# Laser_Shield_Eth.net
KiCad netlist of a schematic drawn in EAGLE
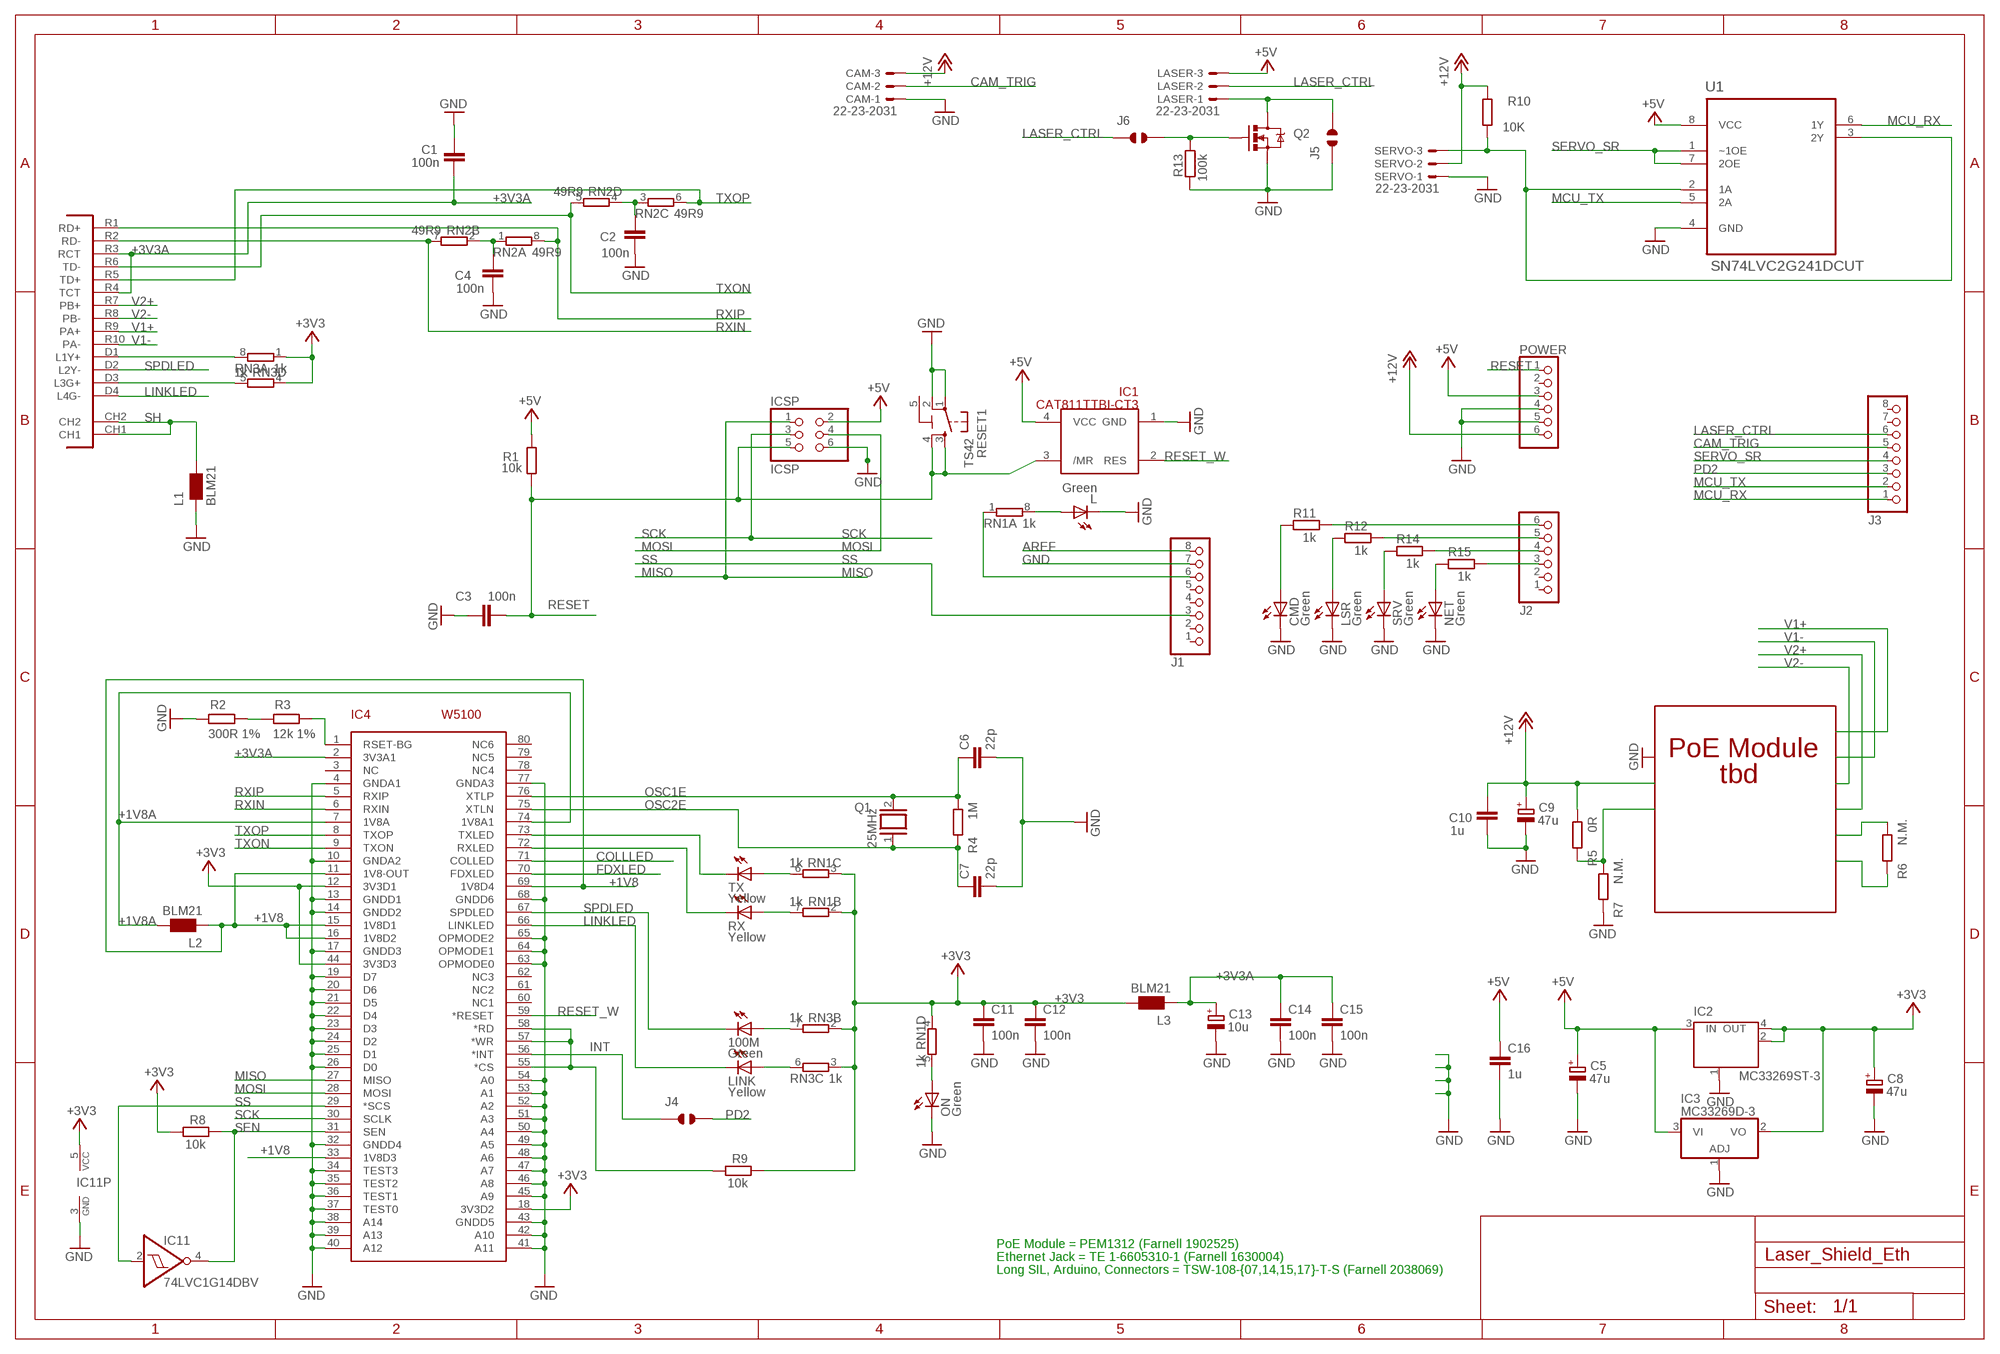
[diagram p0: schematic, sheet 1]

(export (version "E")
  (design (tool "Eeschema 10.0.6"))
  (components
    (comp (ref "100M")
      (value "Green")
      (footprint "eagle-import:CHIPLED_0805")
      (libsource (lib "eagle-import") (part "LEDCHIPLED_0805"))
    )
    (comp (ref "C1")
      (value "100n")
      (footprint "eagle-import:C0603-ROUND")
      (libsource (lib "eagle-import") (part "C-EUC0603"))
    )
    (comp (ref "C2")
      (value "100n")
      (footprint "eagle-import:C0603-ROUND")
      (libsource (lib "eagle-import") (part "C-EUC0603"))
    )
    (comp (ref "C3")
      (value "100n")
      (footprint "eagle-import:C0603-ROUND")
      (libsource (lib "eagle-import") (part "C-EUC0603"))
    )
    (comp (ref "C4")
      (value "100n")
      (footprint "eagle-import:C0603-ROUND")
      (libsource (lib "eagle-import") (part "C-EUC0603"))
    )
    (comp (ref "C5")
      (value "47u")
      (footprint "eagle-import:PANASONIC_D")
      (libsource (lib "eagle-import") (part "CPOL-EUD"))
    )
    (comp (ref "C6")
      (value "22p")
      (footprint "eagle-import:C0603-ROUND")
      (libsource (lib "eagle-import") (part "C-EUC0603"))
    )
    (comp (ref "C7")
      (value "22p")
      (footprint "eagle-import:C0603-ROUND")
      (libsource (lib "eagle-import") (part "C-EUC0603"))
    )
    (comp (ref "C8")
      (value "47u")
      (footprint "eagle-import:PANASONIC_D")
      (libsource (lib "eagle-import") (part "CPOL-EUD"))
    )
    (comp (ref "C9")
      (value "47u")
      (footprint "eagle-import:PANASONIC_D")
      (libsource (lib "eagle-import") (part "CPOL-EUD"))
    )
    (comp (ref "C10")
      (value "1u")
      (footprint "eagle-import:C0603-ROUND")
      (libsource (lib "eagle-import") (part "C-EUC0603"))
    )
    (comp (ref "C11")
      (value "100n")
      (footprint "eagle-import:C0603-ROUND")
      (libsource (lib "eagle-import") (part "C-EUC0603"))
    )
    (comp (ref "C12")
      (value "100n")
      (footprint "eagle-import:C0603-ROUND")
      (libsource (lib "eagle-import") (part "C-EUC0603"))
    )
    (comp (ref "C13")
      (value "10u")
      (footprint "eagle-import:SMC_B")
      (libsource (lib "eagle-import") (part "CPOL-EUSMCB"))
    )
    (comp (ref "C14")
      (value "100n")
      (footprint "eagle-import:C0603-ROUND")
      (libsource (lib "eagle-import") (part "C-EUC0603"))
    )
    (comp (ref "C15")
      (value "100n")
      (footprint "eagle-import:C0603-ROUND")
      (libsource (lib "eagle-import") (part "C-EUC0603"))
    )
    (comp (ref "C16")
      (value "1u")
      (footprint "eagle-import:C0603-ROUND")
      (libsource (lib "eagle-import") (part "C-EUC0603"))
    )
    (comp (ref "CAM")
      (value "22-23-2031")
      (footprint "eagle-import:22-23-2031")
      (fields (field (name "MF") "MOLEX"))
      (libsource (lib "eagle-import") (part "22-23-2031"))
    )
    (comp (ref "CMD")
      (value "Green")
      (footprint "eagle-import:CHIPLED_0805")
      (libsource (lib "eagle-import") (part "LEDCHIPLED_0805"))
    )
    (comp (ref "IC1")
      (value "CAT811TTBI-CT3")
      (footprint "eagle-import:SOT143")
      (fields (field (name "MPN") "STM812LW16F"))
      (libsource (lib "eagle-import") (part "STM812"))
    )
    (comp (ref "IC2")
      (value "MC33269ST-3")
      (footprint "eagle-import:SOT223")
      (libsource (lib "eagle-import") (part "MC33269ST-3.3T3"))
    )
    (comp (ref "IC3")
      (value "MC33269D-3")
      (footprint "eagle-import:DPACK")
      (libsource (lib "eagle-import") (part "MC33269?D-3.3"))
    )
    (comp (ref "IC4")
      (value "W5100")
      (footprint "eagle-import:SQFP-S-10X10-80")
      (libsource (lib "eagle-import") (part "W5100"))
    )
    (comp (ref "IC11")
      (value "74LVC1G14DBV")
      (footprint "eagle-import:SOT23-5")
      (fields (field (name "MPN") "SN74LVC1G14DBVT") (field (name "OC_FARNELL") "1236328"))
      (libsource (lib "eagle-import") (part "741G14DBVLVC"))
    )
    (comp (ref "ICSP")
      (value "ICSP")
      (footprint "eagle-import:2X03")
      (libsource (lib "eagle-import") (part "PINHD-2X3"))
    )
    (comp (ref "J1")
      (value "PINHD-1X8")
      (footprint "eagle-import:1X08")
      (libsource (lib "eagle-import") (part "PINHD-1X8"))
    )
    (comp (ref "J2")
      (value "PINHD-1X6")
      (footprint "eagle-import:1X06")
      (libsource (lib "eagle-import") (part "PINHD-1X6"))
    )
    (comp (ref "J3")
      (value "PINHD-1X8")
      (footprint "eagle-import:1X08")
      (libsource (lib "eagle-import") (part "PINHD-1X8"))
    )
    (comp (ref "J4")
      (value "JUMPER_SOLDER_1X2")
      (footprint "eagle-import:JUMPER_SOLDER_1X2")
      (libsource (lib "eagle-import") (part "JUMPER_SOLDER_1X2"))
    )
    (comp (ref "J5")
      (value "JUMPER_SOLDER_1X2")
      (footprint "eagle-import:JUMPER_SOLDER_1X2")
      (libsource (lib "eagle-import") (part "JUMPER_SOLDER_1X2"))
    )
    (comp (ref "J6")
      (value "JUMPER_SOLDER_1X2")
      (footprint "eagle-import:JUMPER_SOLDER_1X2")
      (libsource (lib "eagle-import") (part "JUMPER_SOLDER_1X2"))
    )
    (comp (ref "L")
      (value "Green")
      (footprint "eagle-import:CHIPLED_0805")
      (libsource (lib "eagle-import") (part "LEDCHIPLED_0805"))
    )
    (comp (ref "L1")
      (value "BLM21")
      (footprint "eagle-import:0805")
      (libsource (lib "eagle-import") (part "WE-CBF_0805"))
    )
    (comp (ref "L2")
      (value "BLM21")
      (footprint "eagle-import:0805")
      (libsource (lib "eagle-import") (part "WE-CBF_0805"))
    )
    (comp (ref "L3")
      (value "BLM21")
      (footprint "eagle-import:0805")
      (libsource (lib "eagle-import") (part "WE-CBF_0805"))
    )
    (comp (ref "LASER")
      (value "22-23-2031")
      (footprint "eagle-import:22-23-2031")
      (fields (field (name "MF") "MOLEX"))
      (libsource (lib "eagle-import") (part "22-23-2031"))
    )
    (comp (ref "LINK")
      (value "Yellow")
      (footprint "eagle-import:CHIPLED_0805")
      (libsource (lib "eagle-import") (part "LEDCHIPLED_0805"))
    )
    (comp (ref "LSR")
      (value "Green")
      (footprint "eagle-import:CHIPLED_0805")
      (libsource (lib "eagle-import") (part "LEDCHIPLED_0805"))
    )
    (comp (ref "NET")
      (value "Green")
      (footprint "eagle-import:CHIPLED_0805")
      (libsource (lib "eagle-import") (part "LEDCHIPLED_0805"))
    )
    (comp (ref "ON")
      (value "Green")
      (footprint "eagle-import:CHIPLED_0805")
      (libsource (lib "eagle-import") (part "LEDCHIPLED_0805"))
    )
    (comp (ref "POWER")
      (value "PINHD-1X6")
      (footprint "eagle-import:1X06")
      (libsource (lib "eagle-import") (part "PINHD-1X6"))
    )
    (comp (ref "Q1")
      (value "25MHz")
      (footprint "eagle-import:QS")
      (libsource (lib "eagle-import") (part "XTAL/S"))
    )
    (comp (ref "Q2")
      (value "MOSFET-NCHANNELSMD")
      (footprint "eagle-import:SOT23-3")
      (libsource (lib "eagle-import") (part "MOSFET-NCHANNELSMD"))
    )
    (comp (ref "R1")
      (value "10k")
      (footprint "eagle-import:R0603-ROUND")
      (libsource (lib "eagle-import") (part "R-EU_0603-RND"))
    )
    (comp (ref "R2")
      (value "300R 1%")
      (footprint "eagle-import:R0603-ROUND")
      (libsource (lib "eagle-import") (part "R-EU_0603-RND"))
    )
    (comp (ref "R3")
      (value "12k 1%")
      (footprint "eagle-import:R0603-ROUND")
      (libsource (lib "eagle-import") (part "R-EU_0603-RND"))
    )
    (comp (ref "R4")
      (value "1M")
      (footprint "eagle-import:R0603-ROUND")
      (libsource (lib "eagle-import") (part "R-EU_0603-RND"))
    )
    (comp (ref "R5")
      (value "0R")
      (footprint "eagle-import:R0603-ROUND")
      (libsource (lib "eagle-import") (part "R-EU_0603-RND"))
    )
    (comp (ref "R6")
      (value "N.M.")
      (footprint "eagle-import:R0603-ROUND")
      (libsource (lib "eagle-import") (part "R-EU_0603-RND"))
    )
    (comp (ref "R7")
      (value "N.M.")
      (footprint "eagle-import:R0603-ROUND")
      (libsource (lib "eagle-import") (part "R-EU_0603-RND"))
    )
    (comp (ref "R8")
      (value "10k")
      (footprint "eagle-import:R0603-ROUND")
      (libsource (lib "eagle-import") (part "R-EU_0603-RND"))
    )
    (comp (ref "R9")
      (value "10k")
      (footprint "eagle-import:R0603-ROUND")
      (libsource (lib "eagle-import") (part "R-EU_R0603"))
    )
    (comp (ref "R10")
      (value "10K")
      (footprint "eagle-import:R0603-ROUND")
      (libsource (lib "eagle-import") (part "R-EU_0603-RND"))
    )
    (comp (ref "R11")
      (value "1k")
      (footprint "eagle-import:R0603-ROUND")
      (libsource (lib "eagle-import") (part "R-EU_R0603"))
    )
    (comp (ref "R12")
      (value "1k")
      (footprint "eagle-import:R0603-ROUND")
      (libsource (lib "eagle-import") (part "R-EU_R0603"))
    )
    (comp (ref "R13")
      (value "100k")
      (footprint "eagle-import:R0603-ROUND")
      (libsource (lib "eagle-import") (part "R-EU_R0603"))
    )
    (comp (ref "R14")
      (value "1k")
      (footprint "eagle-import:R0603-ROUND")
      (libsource (lib "eagle-import") (part "R-EU_R0603"))
    )
    (comp (ref "R15")
      (value "1k")
      (footprint "eagle-import:R0603-ROUND")
      (libsource (lib "eagle-import") (part "R-EU_R0603"))
    )
    (comp (ref "RESET1")
      (value "TS42")
      (footprint "eagle-import:TS42")
      (libsource (lib "eagle-import") (part "TS42"))
    )
    (comp (ref "RN1")
      (value "1k")
      (footprint "eagle-import:CAY16")
      (fields (field (name "MPN") "CAY16-102J4LF") (field (name "OC_FARNELL") "1770133"))
      (libsource (lib "eagle-import") (part "4R-NCAY16"))
    )
    (comp (ref "RN2")
      (value "49R9")
      (footprint "eagle-import:CAY16")
      (fields (field (name "MPN") "CAY16-49R9F4LF") (field (name "OC_FARNELL") "2113092"))
      (libsource (lib "eagle-import") (part "4R-NCAY16"))
    )
    (comp (ref "RN3")
      (value "1k")
      (footprint "eagle-import:CAY16")
      (fields (field (name "MPN") "CAY16-102J4LF") (field (name "OC_FARNELL") "1770133"))
      (libsource (lib "eagle-import") (part "4R-NCAY16"))
    )
    (comp (ref "RX")
      (value "Yellow")
      (footprint "eagle-import:CHIPLED_0805")
      (libsource (lib "eagle-import") (part "LEDCHIPLED_0805"))
    )
    (comp (ref "SERVO")
      (value "22-23-2031")
      (footprint "eagle-import:22-23-2031")
      (fields
        (field (name "MF") "MOLEX")
        (field (name "MPN") "22-03-5035")
        (field (name "OC_FARNELL") "9979620")
      )
      (libsource (lib "eagle-import") (part "22-23-2031"))
    )
    (comp (ref "SRV")
      (value "Green")
      (footprint "eagle-import:CHIPLED_0805")
      (libsource (lib "eagle-import") (part "LEDCHIPLED_0805"))
    )
    (comp (ref "TX")
      (value "Yellow")
      (footprint "eagle-import:CHIPLED_0805")
      (libsource (lib "eagle-import") (part "LEDCHIPLED_0805"))
    )
    (comp (ref "U$1")
      (value "POE-RJ45")
      (footprint "eagle-import:POE-RJ45")
      (libsource (lib "eagle-import") (part "POE-RJ45"))
    )
    (comp (ref "U1")
      (value "SN74LVC2G241DCUT")
      (footprint "eagle-import:SOP50P310X90-8N")
      (libsource (lib "eagle-import") (part "SN74LVC2G241DCUT"))
    )
  )
  (nets
    (net (code "1") (name "+3V3") (class "Default")
      (node (ref "C11") (pin "1") (pinfunction "1_1") (pintype "passive"))
      (node (ref "C12") (pin "1") (pinfunction "1_1") (pintype "passive"))
      (node (ref "C8") (pin "+") (pinfunction "+_+") (pintype "passive"))
      (node (ref "IC11") (pin "5") (pinfunction "VCC_5") (pintype "power_in"))
      (node (ref "IC2") (pin "2") (pinfunction "OUT_2") (pintype "passive"))
      (node (ref "IC2") (pin "4") (pinfunction "OUT_4") (pintype "passive"))
      (node (ref "IC3") (pin "2") (pinfunction "VO_2") (pintype "passive"))
      (node (ref "IC4") (pin "12") (pinfunction "3V3D1_12") (pintype "power_in"))
      (node (ref "IC4") (pin "18") (pinfunction "3V3D2_18") (pintype "power_in"))
      (node (ref "IC4") (pin "44") (pinfunction "3V3D3_44") (pintype "power_in"))
      (node (ref "L3") (pin "2") (pinfunction "2_2") (pintype "passive"))
      (node (ref "R8") (pin "1") (pinfunction "1_1") (pintype "passive"))
      (node (ref "R9") (pin "2") (pinfunction "2_2") (pintype "passive"))
      (node (ref "RN1") (pin "2") (pinfunction "1_2") (pintype "passive"))
      (node (ref "RN1") (pin "3") (pinfunction "1_3") (pintype "passive"))
      (node (ref "RN1") (pin "4") (pinfunction "1_4") (pintype "passive"))
      (node (ref "RN3") (pin "1") (pinfunction "1_1") (pintype "passive"))
      (node (ref "RN3") (pin "2") (pinfunction "1_2") (pintype "passive"))
      (node (ref "RN3") (pin "3") (pinfunction "1_3") (pintype "passive"))
      (node (ref "RN3") (pin "4") (pinfunction "1_4") (pintype "passive"))
    )
    (net (code "2") (name "+5V") (class "Default")
      (node (ref "C16") (pin "1") (pinfunction "1_1") (pintype "passive"))
      (node (ref "C5") (pin "+") (pinfunction "+_+") (pintype "passive"))
      (node (ref "IC1") (pin "4") (pinfunction "VCC_4") (pintype "power_in"))
      (node (ref "IC2") (pin "3") (pinfunction "IN_3") (pintype "input"))
      (node (ref "IC3") (pin "3") (pinfunction "VI_3") (pintype "input"))
      (node (ref "ICSP") (pin "2") (pinfunction "2_2") (pintype "passive"))
      (node (ref "LASER") (pin "3") (pinfunction "S_3") (pintype "passive"))
      (node (ref "POWER") (pin "3") (pinfunction "3_3") (pintype "passive"))
      (node (ref "R1") (pin "2") (pinfunction "2_2") (pintype "passive"))
      (node (ref "U1") (pin "8") (pinfunction "VCC_8") (pintype "power_in"))
    )
    (net (code "3") (name "+12V") (class "Default")
      (node (ref "C10") (pin "2") (pinfunction "2_2") (pintype "passive"))
      (node (ref "C9") (pin "+") (pinfunction "+_+") (pintype "passive"))
      (node (ref "CAM") (pin "3") (pinfunction "S_3") (pintype "passive"))
      (node (ref "POWER") (pin "6") (pinfunction "6_6") (pintype "passive"))
      (node (ref "R10") (pin "1") (pinfunction "1_1") (pintype "passive"))
      (node (ref "R5") (pin "1") (pinfunction "1_1") (pintype "passive"))
      (node (ref "SERVO") (pin "2") (pinfunction "S_2") (pintype "passive"))
    )
    (net (code "4") (name "/+1V8") (class "Default")
      (node (ref "IC4") (pin "11") (pinfunction "1V8-OUT_11") (pintype "power_in"))
      (node (ref "IC4") (pin "15") (pinfunction "1V8D1_15") (pintype "power_in"))
      (node (ref "IC4") (pin "16") (pinfunction "1V8D2_16") (pintype "power_in"))
      (node (ref "IC4") (pin "33") (pinfunction "1V8D3_33") (pintype "power_in"))
      (node (ref "IC4") (pin "69") (pinfunction "1V8D4_69") (pintype "power_in"))
      (node (ref "L2") (pin "1") (pinfunction "1_1") (pintype "passive"))
    )
    (net (code "5") (name "/+1V8A") (class "Default")
      (node (ref "IC4") (pin "7") (pinfunction "1V8A_7") (pintype "power_in"))
      (node (ref "IC4") (pin "74") (pinfunction "1V8A1_74") (pintype "power_in"))
      (node (ref "L2") (pin "2") (pinfunction "2_2") (pintype "passive"))
    )
    (net (code "6") (name "/+3V3A") (class "Default")
      (node (ref "C1") (pin "1") (pinfunction "1_1") (pintype "passive"))
      (node (ref "C13") (pin "+") (pinfunction "+_+") (pintype "passive"))
      (node (ref "C14") (pin "1") (pinfunction "1_1") (pintype "passive"))
      (node (ref "C15") (pin "1") (pinfunction "1_1") (pintype "passive"))
      (node (ref "IC4") (pin "2") (pinfunction "3V3A1_2") (pintype "power_in"))
      (node (ref "L3") (pin "1") (pinfunction "1_1") (pintype "passive"))
      (node (ref "U$1") (pin "R3") (pinfunction "RCT_R3") (pintype "bidirectional"))
      (node (ref "U$1") (pin "R4") (pinfunction "TCT_R4") (pintype "bidirectional"))
    )
    (net (code "7") (name "/5-GND") (class "Default")
      (node (ref "RESET1") (pin "5") (pinfunction "5-GND_5") (pintype "power_in"))
    )
    (net (code "8") (name "/AREF") (class "Default")
      (node (ref "J1") (pin "8") (pinfunction "8_8") (pintype "passive"))
    )
    (net (code "9") (name "/CAM_TRIG") (class "Default")
      (node (ref "CAM") (pin "2") (pinfunction "S_2") (pintype "passive"))
      (node (ref "J3") (pin "5") (pinfunction "5_5") (pintype "passive"))
    )
    (net (code "10") (name "/COLLLED") (class "Default")
      (node (ref "IC4") (pin "71") (pinfunction "COLLED_71") (pintype "output"))
    )
    (net (code "11") (name "/FDXLED") (class "Default")
      (node (ref "IC4") (pin "70") (pinfunction "FDXLED_70") (pintype "output"))
    )
    (net (code "12") (name "/INT") (class "Default")
      (node (ref "IC4") (pin "56") (pinfunction "*INT_56") (pintype "input"))
      (node (ref "J4") (pin "1") (pinfunction "1_1") (pintype "passive"))
    )
    (net (code "13") (name "/LASER_CTRL") (class "Default")
      (node (ref "J3") (pin "6") (pinfunction "6_6") (pintype "passive"))
      (node (ref "J6") (pin "1") (pinfunction "1_1") (pintype "passive"))
      (node (ref "LASER") (pin "2") (pinfunction "S_2") (pintype "passive"))
    )
    (net (code "14") (name "/LINKLED") (class "Default")
      (node (ref "IC4") (pin "66") (pinfunction "LINKLED_66") (pintype "output"))
      (node (ref "LINK") (pin "C") (pinfunction "C_C") (pintype "passive"))
      (node (ref "U$1") (pin "D4") (pinfunction "L4G-_D4") (pintype "bidirectional"))
    )
    (net (code "15") (name "/MCU_RX") (class "Default")
      (node (ref "J3") (pin "1") (pinfunction "1_1") (pintype "passive"))
      (node (ref "U1") (pin "6") (pinfunction "1Y_6") (pintype "output"))
    )
    (net (code "16") (name "/MCU_TX") (class "Default")
      (node (ref "J3") (pin "2") (pinfunction "2_2") (pintype "passive"))
      (node (ref "U1") (pin "5") (pinfunction "2A_5") (pintype "input"))
    )
    (net (code "17") (name "/MISO") (class "Default")
      (node (ref "IC4") (pin "27") (pinfunction "MISO_27") (pintype "input"))
      (node (ref "ICSP") (pin "1") (pinfunction "1_1") (pintype "passive"))
    )
    (net (code "18") (name "/MOSI") (class "Default")
      (node (ref "IC4") (pin "28") (pinfunction "MOSI_28") (pintype "output"))
      (node (ref "ICSP") (pin "4") (pinfunction "4_4") (pintype "passive"))
    )
    (net (code "19") (name "/OSC1E") (class "Default")
      (node (ref "C6") (pin "1") (pinfunction "1_1") (pintype "passive"))
      (node (ref "IC4") (pin "76") (pinfunction "XTLP_76") (pintype "output"))
      (node (ref "Q1") (pin "2") (pinfunction "2_2") (pintype "passive"))
      (node (ref "R4") (pin "1") (pinfunction "1_1") (pintype "passive"))
    )
    (net (code "20") (name "/OSC2E") (class "Default")
      (node (ref "C7") (pin "1") (pinfunction "1_1") (pintype "passive"))
      (node (ref "IC4") (pin "75") (pinfunction "XTLN_75") (pintype "output"))
      (node (ref "Q1") (pin "1") (pinfunction "1_1") (pintype "passive"))
      (node (ref "R4") (pin "2") (pinfunction "2_2") (pintype "passive"))
    )
    (net (code "21") (name "/PD2") (class "Default")
      (node (ref "J3") (pin "3") (pinfunction "3_3") (pintype "passive"))
      (node (ref "J4") (pin "2") (pinfunction "2_2") (pintype "passive"))
    )
    (net (code "22") (name "/RESET") (class "Default")
      (node (ref "C3") (pin "1") (pinfunction "1_1") (pintype "passive"))
      (node (ref "IC1") (pin "3") (pinfunction "/MR_3") (pintype "input"))
      (node (ref "ICSP") (pin "5") (pinfunction "5_5") (pintype "passive"))
      (node (ref "POWER") (pin "1") (pinfunction "1_1") (pintype "passive"))
      (node (ref "R1") (pin "1") (pinfunction "1_1") (pintype "passive"))
      (node (ref "RESET1") (pin "3") (pinfunction "3_3") (pintype "passive"))
      (node (ref "RESET1") (pin "4") (pinfunction "4_4") (pintype "passive"))
    )
    (net (code "23") (name "/RESET_W") (class "Default")
      (node (ref "IC1") (pin "2") (pinfunction "RES_2") (pintype "output"))
      (node (ref "IC4") (pin "59") (pinfunction "*RESET_59") (pintype "input"))
    )
    (net (code "24") (name "/RXIN") (class "Default")
      (node (ref "IC4") (pin "6") (pinfunction "RXIN_6") (pintype "input"))
      (node (ref "RN2") (pin "7") (pinfunction "2_7") (pintype "passive"))
      (node (ref "U$1") (pin "R2") (pinfunction "RD-_R2") (pintype "bidirectional"))
    )
    (net (code "25") (name "/RXIP") (class "Default")
      (node (ref "IC4") (pin "5") (pinfunction "RXIP_5") (pintype "input"))
      (node (ref "RN2") (pin "8") (pinfunction "2_8") (pintype "passive"))
      (node (ref "U$1") (pin "R1") (pinfunction "RD+_R1") (pintype "bidirectional"))
    )
    (net (code "26") (name "/SCK") (class "Default")
      (node (ref "IC4") (pin "30") (pinfunction "SCLK_30") (pintype "input"))
      (node (ref "ICSP") (pin "3") (pinfunction "3_3") (pintype "passive"))
    )
    (net (code "27") (name "/SEN") (class "Default")
      (node (ref "IC11") (pin "4") (pinfunction "O_4") (pintype "output"))
      (node (ref "IC4") (pin "31") (pinfunction "SEN_31") (pintype "input"))
      (node (ref "R8") (pin "2") (pinfunction "2_2") (pintype "passive"))
    )
    (net (code "28") (name "/SERVO_SR") (class "Default")
      (node (ref "J3") (pin "4") (pinfunction "4_4") (pintype "passive"))
      (node (ref "U1") (pin "1") (pinfunction "~{1OE}_1") (pintype "input"))
      (node (ref "U1") (pin "7") (pinfunction "2OE_7") (pintype "input"))
    )
    (net (code "29") (name "/SH") (class "Default")
      (node (ref "L1") (pin "2") (pinfunction "2_2") (pintype "passive"))
      (node (ref "U$1") (pin "CH1") (pinfunction "CH1_CH1") (pintype "bidirectional"))
      (node (ref "U$1") (pin "CH2") (pinfunction "CH2_CH2") (pintype "bidirectional"))
    )
    (net (code "30") (name "/SPDLED") (class "Default")
      (node (ref "100M") (pin "C") (pinfunction "C_C") (pintype "passive"))
      (node (ref "IC4") (pin "67") (pinfunction "SPDLED_67") (pintype "output"))
      (node (ref "U$1") (pin "D2") (pinfunction "L2Y-_D2") (pintype "bidirectional"))
    )
    (net (code "31") (name "/SS") (class "Default")
      (node (ref "IC11") (pin "2") (pinfunction "I_2") (pintype "input"))
      (node (ref "IC4") (pin "29") (pinfunction "*SCS_29") (pintype "input"))
      (node (ref "J1") (pin "3") (pinfunction "3_3") (pintype "passive"))
    )
    (net (code "32") (name "/TXON") (class "Default")
      (node (ref "IC4") (pin "9") (pinfunction "TXON_9") (pintype "output"))
      (node (ref "RN2") (pin "5") (pinfunction "2_5") (pintype "passive"))
      (node (ref "U$1") (pin "R6") (pinfunction "TD-_R6") (pintype "bidirectional"))
    )
    (net (code "33") (name "/TXOP") (class "Default")
      (node (ref "IC4") (pin "8") (pinfunction "TXOP_8") (pintype "output"))
      (node (ref "RN2") (pin "6") (pinfunction "2_6") (pintype "passive"))
      (node (ref "U$1") (pin "R5") (pinfunction "TD+_R5") (pintype "bidirectional"))
    )
    (net (code "34") (name "/V1+") (class "Default")
      (node (ref "U$1") (pin "R9") (pinfunction "PA+_R9") (pintype "bidirectional"))
    )
    (net (code "35") (name "/V1-") (class "Default")
      (node (ref "U$1") (pin "R10") (pinfunction "PA-_R10") (pintype "bidirectional"))
    )
    (net (code "36") (name "/V2+") (class "Default")
      (node (ref "U$1") (pin "R7") (pinfunction "PB+_R7") (pintype "bidirectional"))
    )
    (net (code "37") (name "/V2-") (class "Default")
      (node (ref "U$1") (pin "R8") (pinfunction "PB-_R8") (pintype "bidirectional"))
    )
    (net (code "38") (name "GND") (class "Default")
      (node (ref "C1") (pin "2") (pinfunction "2_2") (pintype "passive"))
      (node (ref "C10") (pin "1") (pinfunction "1_1") (pintype "passive"))
      (node (ref "C11") (pin "2") (pinfunction "2_2") (pintype "passive"))
      (node (ref "C12") (pin "2") (pinfunction "2_2") (pintype "passive"))
      (node (ref "C13") (pin "-") (pinfunction "-_-") (pintype "passive"))
      (node (ref "C14") (pin "2") (pinfunction "2_2") (pintype "passive"))
      (node (ref "C15") (pin "2") (pinfunction "2_2") (pintype "passive"))
      (node (ref "C16") (pin "2") (pinfunction "2_2") (pintype "passive"))
      (node (ref "C2") (pin "1") (pinfunction "1_1") (pintype "passive"))
      (node (ref "C3") (pin "2") (pinfunction "2_2") (pintype "passive"))
      (node (ref "C4") (pin "1") (pinfunction "1_1") (pintype "passive"))
      (node (ref "C5") (pin "-") (pinfunction "-_-") (pintype "passive"))
      (node (ref "C6") (pin "2") (pinfunction "2_2") (pintype "passive"))
      (node (ref "C7") (pin "2") (pinfunction "2_2") (pintype "passive"))
      (node (ref "C8") (pin "-") (pinfunction "-_-") (pintype "passive"))
      (node (ref "C9") (pin "-") (pinfunction "-_-") (pintype "passive"))
      (node (ref "CAM") (pin "1") (pinfunction "S_1") (pintype "passive"))
      (node (ref "CMD") (pin "C") (pinfunction "C_C") (pintype "passive"))
      (node (ref "IC1") (pin "1") (pinfunction "GND_1") (pintype "power_in"))
      (node (ref "IC11") (pin "3") (pinfunction "GND_3") (pintype "power_in"))
      (node (ref "IC2") (pin "1") (pinfunction "GND/ADJ_1") (pintype "input"))
      (node (ref "IC3") (pin "1") (pinfunction "ADJ_1") (pintype "input"))
      (node (ref "IC4") (pin "10") (pinfunction "GNDA2_10") (pintype "power_in"))
      (node (ref "IC4") (pin "13") (pinfunction "GNDD1_13") (pintype "power_in"))
      (node (ref "IC4") (pin "14") (pinfunction "GNDD2_14") (pintype "power_in"))
      (node (ref "IC4") (pin "17") (pinfunction "GNDD3_17") (pintype "power_in"))
      (node (ref "IC4") (pin "19") (pinfunction "D7_19") (pintype "input"))
      (node (ref "IC4") (pin "20") (pinfunction "D6_20") (pintype "input"))
      (node (ref "IC4") (pin "21") (pinfunction "D5_21") (pintype "input"))
      (node (ref "IC4") (pin "22") (pinfunction "D4_22") (pintype "input"))
      (node (ref "IC4") (pin "23") (pinfunction "D3_23") (pintype "input"))
      (node (ref "IC4") (pin "24") (pinfunction "D2_24") (pintype "input"))
      (node (ref "IC4") (pin "25") (pinfunction "D1_25") (pintype "input"))
      (node (ref "IC4") (pin "26") (pinfunction "D0_26") (pintype "input"))
      (node (ref "IC4") (pin "32") (pinfunction "GNDD4_32") (pintype "power_in"))
      (node (ref "IC4") (pin "34") (pinfunction "TEST3_34") (pintype "input"))
      (node (ref "IC4") (pin "35") (pinfunction "TEST2_35") (pintype "input"))
      (node (ref "IC4") (pin "36") (pinfunction "TEST1_36") (pintype "input"))
      (node (ref "IC4") (pin "37") (pinfunction "TEST0_37") (pintype "input"))
      (node (ref "IC4") (pin "38") (pinfunction "A14_38") (pintype "input"))
      (node (ref "IC4") (pin "39") (pinfunction "A13_39") (pintype "input"))
      (node (ref "IC4") (pin "4") (pinfunction "GNDA1_4") (pintype "power_in"))
      (node (ref "IC4") (pin "40") (pinfunction "A12_40") (pintype "input"))
      (node (ref "IC4") (pin "41") (pinfunction "A11_41") (pintype "input"))
      (node (ref "IC4") (pin "42") (pinfunction "A10_42") (pintype "input"))
      (node (ref "IC4") (pin "43") (pinfunction "GNDD5_43") (pintype "power_in"))
      (node (ref "IC4") (pin "45") (pinfunction "A9_45") (pintype "input"))
      (node (ref "IC4") (pin "46") (pinfunction "A8_46") (pintype "input"))
      (node (ref "IC4") (pin "47") (pinfunction "A7_47") (pintype "input"))
      (node (ref "IC4") (pin "48") (pinfunction "A6_48") (pintype "input"))
      (node (ref "IC4") (pin "49") (pinfunction "A5_49") (pintype "input"))
      (node (ref "IC4") (pin "50") (pinfunction "A4_50") (pintype "input"))
      (node (ref "IC4") (pin "51") (pinfunction "A3_51") (pintype "input"))
      (node (ref "IC4") (pin "52") (pinfunction "A2_52") (pintype "input"))
      (node (ref "IC4") (pin "53") (pinfunction "A1_53") (pintype "input"))
      (node (ref "IC4") (pin "54") (pinfunction "A0_54") (pintype "input"))
      (node (ref "IC4") (pin "63") (pinfunction "OPMODE0_63") (pintype "input"))
      (node (ref "IC4") (pin "64") (pinfunction "OPMODE1_64") (pintype "input"))
      (node (ref "IC4") (pin "65") (pinfunction "OPMODE2_65") (pintype "input"))
      (node (ref "IC4") (pin "68") (pinfunction "GNDD6_68") (pintype "power_in"))
      (node (ref "IC4") (pin "77") (pinfunction "GNDA3_77") (pintype "power_in"))
      (node (ref "ICSP") (pin "6") (pinfunction "6_6") (pintype "passive"))
      (node (ref "J1") (pin "7") (pinfunction "7_7") (pintype "passive"))
      (node (ref "J5") (pin "1") (pinfunction "1_1") (pintype "passive"))
      (node (ref "L") (pin "C") (pinfunction "C_C") (pintype "passive"))
      (node (ref "L1") (pin "1") (pinfunction "1_1") (pintype "passive"))
      (node (ref "LSR") (pin "C") (pinfunction "C_C") (pintype "passive"))
      (node (ref "NET") (pin "C") (pinfunction "C_C") (pintype "passive"))
      (node (ref "ON") (pin "C") (pinfunction "C_C") (pintype "passive"))
      (node (ref "POWER") (pin "4") (pinfunction "4_4") (pintype "passive"))
      (node (ref "POWER") (pin "5") (pinfunction "5_5") (pintype "passive"))
      (node (ref "Q2") (pin "2") (pinfunction "S_2") (pintype "passive"))
      (node (ref "R13") (pin "1") (pinfunction "1_1") (pintype "passive"))
      (node (ref "R2") (pin "2") (pinfunction "2_2") (pintype "passive"))
      (node (ref "R7") (pin "2") (pinfunction "2_2") (pintype "passive"))
      (node (ref "RESET1") (pin "1") (pinfunction "1_1") (pintype "passive"))
      (node (ref "RESET1") (pin "2") (pinfunction "2_2") (pintype "passive"))
      (node (ref "SERVO") (pin "1") (pinfunction "S_1") (pintype "passive"))
      (node (ref "SRV") (pin "C") (pinfunction "C_C") (pintype "passive"))
      (node (ref "U1") (pin "4") (pinfunction "GND_4") (pintype "passive"))
    )
    (net (code "39") (name "Net-(CMD-PadA)") (class "Default")
      (node (ref "CMD") (pin "A") (pinfunction "A_A") (pintype "passive"))
      (node (ref "R11") (pin "1") (pinfunction "1_1") (pintype "passive"))
    )
    (net (code "40") (name "Net-(IC4-*CS)") (class "Default")
      (node (ref "IC4") (pin "55") (pinfunction "*CS_55") (pintype "input"))
      (node (ref "IC4") (pin "57") (pinfunction "*WR_57") (pintype "input"))
      (node (ref "IC4") (pin "58") (pinfunction "*RD_58") (pintype "input"))
      (node (ref "R9") (pin "1") (pinfunction "1_1") (pintype "passive"))
    )
    (net (code "41") (name "Net-(IC4-RSET-BG)") (class "Default")
      (node (ref "IC4") (pin "1") (pinfunction "RSET-BG_1") (pintype "input"))
      (node (ref "R3") (pin "1") (pinfunction "1_1") (pintype "passive"))
    )
    (net (code "42") (name "Net-(IC4-RXLED)") (class "Default")
      (node (ref "IC4") (pin "72") (pinfunction "RXLED_72") (pintype "output"))
      (node (ref "RX") (pin "C") (pinfunction "C_C") (pintype "passive"))
    )
    (net (code "43") (name "Net-(IC4-TXLED)") (class "Default")
      (node (ref "IC4") (pin "73") (pinfunction "TXLED_73") (pintype "output"))
      (node (ref "TX") (pin "C") (pinfunction "C_C") (pintype "passive"))
    )
    (net (code "44") (name "Net-(J1-Pad6)") (class "Default")
      (node (ref "J1") (pin "6") (pinfunction "6_6") (pintype "passive"))
      (node (ref "RN1") (pin "1") (pinfunction "1_1") (pintype "passive"))
    )
    (net (code "45") (name "Net-(J2-Pad3)") (class "Default")
      (node (ref "J2") (pin "3") (pinfunction "3_3") (pintype "passive"))
      (node (ref "R15") (pin "2") (pinfunction "2_2") (pintype "passive"))
    )
    (net (code "46") (name "Net-(J2-Pad4)") (class "Default")
      (node (ref "J2") (pin "4") (pinfunction "4_4") (pintype "passive"))
      (node (ref "R14") (pin "2") (pinfunction "2_2") (pintype "passive"))
    )
    (net (code "47") (name "Net-(J2-Pad5)") (class "Default")
      (node (ref "J2") (pin "5") (pinfunction "5_5") (pintype "passive"))
      (node (ref "R12") (pin "2") (pinfunction "2_2") (pintype "passive"))
    )
    (net (code "48") (name "Net-(J2-Pad6)") (class "Default")
      (node (ref "J2") (pin "6") (pinfunction "6_6") (pintype "passive"))
      (node (ref "R11") (pin "2") (pinfunction "2_2") (pintype "passive"))
    )
    (net (code "49") (name "Net-(LASERA-S)") (class "Default")
      (node (ref "J5") (pin "2") (pinfunction "2_2") (pintype "passive"))
      (node (ref "LASER") (pin "1") (pinfunction "S_1") (pintype "passive"))
      (node (ref "Q2") (pin "3") (pinfunction "D_3") (pintype "passive"))
    )
    (net (code "50") (name "Net-(LSR-PadA)") (class "Default")
      (node (ref "LSR") (pin "A") (pinfunction "A_A") (pintype "passive"))
      (node (ref "R12") (pin "1") (pinfunction "1_1") (pintype "passive"))
    )
    (net (code "51") (name "Net-(NET-PadA)") (class "Default")
      (node (ref "NET") (pin "A") (pinfunction "A_A") (pintype "passive"))
      (node (ref "R15") (pin "1") (pinfunction "1_1") (pintype "passive"))
    )
    (net (code "52") (name "Net-(Q2-G)") (class "Default")
      (node (ref "J6") (pin "2") (pinfunction "2_2") (pintype "passive"))
      (node (ref "Q2") (pin "1") (pinfunction "G_1") (pintype "passive"))
      (node (ref "R13") (pin "2") (pinfunction "2_2") (pintype "passive"))
    )
    (net (code "53") (name "Net-(R2-Pad1)") (class "Default")
      (node (ref "R2") (pin "1") (pinfunction "1_1") (pintype "passive"))
      (node (ref "R3") (pin "2") (pinfunction "2_2") (pintype "passive"))
    )
    (net (code "54") (name "Net-(R5-Pad2)") (class "Default")
      (node (ref "R5") (pin "2") (pinfunction "2_2") (pintype "passive"))
      (node (ref "R7") (pin "1") (pinfunction "1_1") (pintype "passive"))
    )
    (net (code "55") (name "Net-(R14-Pad1)") (class "Default")
      (node (ref "R14") (pin "1") (pinfunction "1_1") (pintype "passive"))
      (node (ref "SRV") (pin "A") (pinfunction "A_A") (pintype "passive"))
    )
    (net (code "56") (name "Net-(RN1A-2)") (class "Default")
      (node (ref "L") (pin "A") (pinfunction "A_A") (pintype "passive"))
      (node (ref "RN1") (pin "8") (pinfunction "2_8") (pintype "passive"))
    )
    (net (code "57") (name "Net-(RN1B-2)") (class "Default")
      (node (ref "RN1") (pin "7") (pinfunction "2_7") (pintype "passive"))
      (node (ref "RX") (pin "A") (pinfunction "A_A") (pintype "passive"))
    )
    (net (code "58") (name "Net-(RN1C-2)") (class "Default")
      (node (ref "RN1") (pin "6") (pinfunction "2_6") (pintype "passive"))
      (node (ref "TX") (pin "A") (pinfunction "A_A") (pintype "passive"))
    )
    (net (code "59") (name "Net-(RN1D-2)") (class "Default")
      (node (ref "ON") (pin "A") (pinfunction "A_A") (pintype "passive"))
      (node (ref "RN1") (pin "5") (pinfunction "2_5") (pintype "passive"))
    )
    (net (code "60") (name "Net-(RN2B-1)") (class "Default")
      (node (ref "C4") (pin "2") (pinfunction "2_2") (pintype "passive"))
      (node (ref "RN2") (pin "1") (pinfunction "1_1") (pintype "passive"))
      (node (ref "RN2") (pin "2") (pinfunction "1_2") (pintype "passive"))
    )
    (net (code "61") (name "Net-(RN2C-1)") (class "Default")
      (node (ref "C2") (pin "2") (pinfunction "2_2") (pintype "passive"))
      (node (ref "RN2") (pin "3") (pinfunction "1_3") (pintype "passive"))
      (node (ref "RN2") (pin "4") (pinfunction "1_4") (pintype "passive"))
    )
    (net (code "62") (name "Net-(RN3A-2)") (class "Default")
      (node (ref "RN3") (pin "8") (pinfunction "2_8") (pintype "passive"))
      (node (ref "U$1") (pin "D1") (pinfunction "L1Y+_D1") (pintype "bidirectional"))
    )
    (net (code "63") (name "Net-(RN3B-2)") (class "Default")
      (node (ref "100M") (pin "A") (pinfunction "A_A") (pintype "passive"))
      (node (ref "RN3") (pin "7") (pinfunction "2_7") (pintype "passive"))
    )
    (net (code "64") (name "Net-(RN3C-2)") (class "Default")
      (node (ref "LINK") (pin "A") (pinfunction "A_A") (pintype "passive"))
      (node (ref "RN3") (pin "6") (pinfunction "2_6") (pintype "passive"))
    )
    (net (code "65") (name "Net-(RN3D-2)") (class "Default")
      (node (ref "RN3") (pin "5") (pinfunction "2_5") (pintype "passive"))
      (node (ref "U$1") (pin "D3") (pinfunction "L3G+_D3") (pintype "bidirectional"))
    )
    (net (code "66") (name "Net-(SERVOC-S)") (class "Default")
      (node (ref "R10") (pin "2") (pinfunction "2_2") (pintype "passive"))
      (node (ref "SERVO") (pin "3") (pinfunction "S_3") (pintype "passive"))
      (node (ref "U1") (pin "2") (pinfunction "1A_2") (pintype "input"))
      (node (ref "U1") (pin "3") (pinfunction "2Y_3") (pintype "output"))
    )
    (net (code "67") (name "unconnected-(IC4-NC-Pad3)") (class "Default")
      (node (ref "IC4") (pin "3") (pinfunction "NC_3") (pintype "no_connect"))
    )
    (net (code "68") (name "unconnected-(IC4-NC1-Pad60)") (class "Default")
      (node (ref "IC4") (pin "60") (pinfunction "NC1_60") (pintype "no_connect"))
    )
    (net (code "69") (name "unconnected-(IC4-NC2-Pad61)") (class "Default")
      (node (ref "IC4") (pin "61") (pinfunction "NC2_61") (pintype "no_connect"))
    )
    (net (code "70") (name "unconnected-(IC4-NC3-Pad62)") (class "Default")
      (node (ref "IC4") (pin "62") (pinfunction "NC3_62") (pintype "no_connect"))
    )
    (net (code "71") (name "unconnected-(IC4-NC4-Pad78)") (class "Default")
      (node (ref "IC4") (pin "78") (pinfunction "NC4_78") (pintype "no_connect"))
    )
    (net (code "72") (name "unconnected-(IC4-NC5-Pad79)") (class "Default")
      (node (ref "IC4") (pin "79") (pinfunction "NC5_79") (pintype "no_connect"))
    )
    (net (code "73") (name "unconnected-(IC4-NC6-Pad80)") (class "Default")
      (node (ref "IC4") (pin "80") (pinfunction "NC6_80") (pintype "no_connect"))
    )
    (net (code "74") (name "unconnected-(J1-Pad1)") (class "Default")
      (node (ref "J1") (pin "1") (pinfunction "1_1") (pintype "passive"))
    )
    (net (code "75") (name "unconnected-(J1-Pad2)") (class "Default")
      (node (ref "J1") (pin "2") (pinfunction "2_2") (pintype "passive"))
    )
    (net (code "76") (name "unconnected-(J1-Pad4)") (class "Default")
      (node (ref "J1") (pin "4") (pinfunction "4_4") (pintype "passive"))
    )
    (net (code "77") (name "unconnected-(J1-Pad5)") (class "Default")
      (node (ref "J1") (pin "5") (pinfunction "5_5") (pintype "passive"))
    )
    (net (code "78") (name "unconnected-(J2-Pad1)") (class "Default")
      (node (ref "J2") (pin "1") (pinfunction "1_1") (pintype "passive"))
    )
    (net (code "79") (name "unconnected-(J2-Pad2)") (class "Default")
      (node (ref "J2") (pin "2") (pinfunction "2_2") (pintype "passive"))
    )
    (net (code "80") (name "unconnected-(J3-Pad7)") (class "Default")
      (node (ref "J3") (pin "7") (pinfunction "7_7") (pintype "passive"))
    )
    (net (code "81") (name "unconnected-(J3-Pad8)") (class "Default")
      (node (ref "J3") (pin "8") (pinfunction "8_8") (pintype "passive"))
    )
    (net (code "82") (name "unconnected-(POWER-Pad2)") (class "Default")
      (node (ref "POWER") (pin "2") (pinfunction "2_2") (pintype "passive"))
    )
    (net (code "83") (name "unconnected-(R6-Pad1)") (class "Default")
      (node (ref "R6") (pin "1") (pinfunction "1_1") (pintype "passive"))
    )
    (net (code "84") (name "unconnected-(R6-Pad2)") (class "Default")
      (node (ref "R6") (pin "2") (pinfunction "2_2") (pintype "passive"))
    )
  )
)
